# FIIDO_D2_SDA_SCL.net
KiCad netlist of a schematic drawn in EAGLE
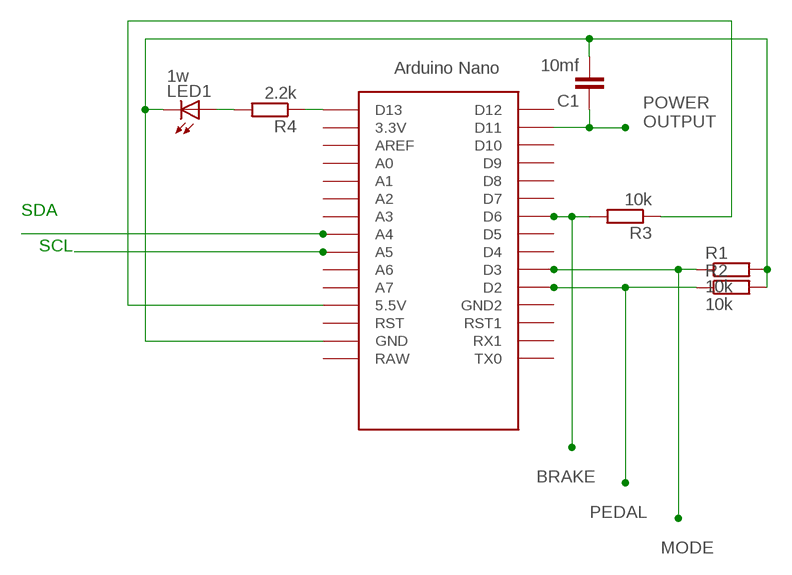
[diagram p0: schematic, sheet 1]

(export (version "E")
  (design (tool "Eeschema 10.0.6"))
  (components
    (comp (ref "C1")
      (value "10mf")
      (footprint "eagle-import:C025-024X044")
      (libsource (lib "eagle-import") (part "C-EU025-024X044"))
    )
    (comp (ref "LED1")
      (value "1w")
      (footprint "eagle-import:LED3MM")
      (libsource (lib "eagle-import") (part "LED3MM"))
    )
    (comp (ref "R1")
      (value "10k")
      (footprint "eagle-import:0207_5V")
      (libsource (lib "eagle-import") (part "R-EU_0207/5V"))
    )
    (comp (ref "R2")
      (value "10k")
      (footprint "eagle-import:0207_5V")
      (libsource (lib "eagle-import") (part "R-EU_0207/5V"))
    )
    (comp (ref "R3")
      (value "10k")
      (footprint "eagle-import:0207_5V")
      (libsource (lib "eagle-import") (part "R-EU_0207/5V"))
    )
    (comp (ref "R4")
      (value "2.2k")
      (footprint "eagle-import:0207_5V")
      (libsource (lib "eagle-import") (part "R-EU_0207/5V"))
    )
    (comp (ref "U$1")
      (value "NANO")
      (footprint "eagle-import:NANO")
      (libsource (lib "eagle-import") (part "NANO"))
    )
  )
  (nets
    (net (code "1") (name "Net-(C1-Pad1)") (class "Default")
      (node (ref "C1") (pin "1") (pinfunction "1_1") (pintype "passive"))
      (node (ref "U$1") (pin "D11") (pinfunction "D11_D11") (pintype "bidirectional"))
    )
    (net (code "2") (name "Net-(LED1-C)") (class "Default")
      (node (ref "C1") (pin "2") (pinfunction "2_2") (pintype "passive"))
      (node (ref "LED1") (pin "K") (pinfunction "C_K") (pintype "passive"))
      (node (ref "R1") (pin "2") (pinfunction "2_2") (pintype "passive"))
      (node (ref "R2") (pin "2") (pinfunction "2_2") (pintype "passive"))
      (node (ref "U$1") (pin "GND") (pinfunction "GND_GND") (pintype "bidirectional"))
    )
    (net (code "3") (name "Net-(LED1-PadA)") (class "Default")
      (node (ref "LED1") (pin "A") (pinfunction "A_A") (pintype "passive"))
      (node (ref "R4") (pin "2") (pinfunction "2_2") (pintype "passive"))
    )
    (net (code "4") (name "Net-(R1-Pad1)") (class "Default")
      (node (ref "R1") (pin "1") (pinfunction "1_1") (pintype "passive"))
      (node (ref "U$1") (pin "D3") (pinfunction "D3_D3") (pintype "bidirectional"))
    )
    (net (code "5") (name "Net-(R2-Pad1)") (class "Default")
      (node (ref "R2") (pin "1") (pinfunction "1_1") (pintype "passive"))
      (node (ref "U$1") (pin "D2") (pinfunction "D2_D2") (pintype "bidirectional"))
    )
    (net (code "6") (name "Net-(R3-Pad2)") (class "Default")
      (node (ref "R3") (pin "2") (pinfunction "2_2") (pintype "passive"))
      (node (ref "U$1") (pin "D6") (pinfunction "D6_D6") (pintype "bidirectional"))
    )
    (net (code "7") (name "Net-(R4-Pad1)") (class "Default")
      (node (ref "R4") (pin "1") (pinfunction "1_1") (pintype "passive"))
      (node (ref "U$1") (pin "D13") (pinfunction "D13_D13") (pintype "bidirectional"))
    )
    (net (code "8") (name "Net-(U$1-5.5V)") (class "Default")
      (node (ref "R3") (pin "1") (pinfunction "1_1") (pintype "passive"))
      (node (ref "U$1") (pin "5V") (pinfunction "5.5V_5V") (pintype "bidirectional"))
    )
    (net (code "9") (name "unconnected-(U$1-GND2-PadGND1)") (class "Default")
      (node (ref "U$1") (pin "GND1") (pinfunction "GND2_GND1") (pintype "bidirectional"))
    )
    (net (code "10") (name "unconnected-(U$1-Pad3.3V)") (class "Default")
      (node (ref "U$1") (pin "3.3V") (pinfunction "3.3V_3.3V") (pintype "bidirectional"))
    )
    (net (code "11") (name "unconnected-(U$1-PadA0)") (class "Default")
      (node (ref "U$1") (pin "A0") (pinfunction "A0_A0") (pintype "bidirectional"))
    )
    (net (code "12") (name "unconnected-(U$1-PadA1)") (class "Default")
      (node (ref "U$1") (pin "A1") (pinfunction "A1_A1") (pintype "bidirectional"))
    )
    (net (code "13") (name "unconnected-(U$1-PadA2)") (class "Default")
      (node (ref "U$1") (pin "A2") (pinfunction "A2_A2") (pintype "bidirectional"))
    )
    (net (code "14") (name "unconnected-(U$1-PadA3)") (class "Default")
      (node (ref "U$1") (pin "A3") (pinfunction "A3_A3") (pintype "bidirectional"))
    )
    (net (code "15") (name "unconnected-(U$1-PadA4)") (class "Default")
      (node (ref "U$1") (pin "A4") (pinfunction "A4_A4") (pintype "bidirectional"))
    )
    (net (code "16") (name "unconnected-(U$1-PadA5)") (class "Default")
      (node (ref "U$1") (pin "A5") (pinfunction "A5_A5") (pintype "bidirectional"))
    )
    (net (code "17") (name "unconnected-(U$1-PadA6)") (class "Default")
      (node (ref "U$1") (pin "A6") (pinfunction "A6_A6") (pintype "bidirectional"))
    )
    (net (code "18") (name "unconnected-(U$1-PadA7)") (class "Default")
      (node (ref "U$1") (pin "A7") (pinfunction "A7_A7") (pintype "bidirectional"))
    )
    (net (code "19") (name "unconnected-(U$1-PadAREF)") (class "Default")
      (node (ref "U$1") (pin "AREF") (pinfunction "AREF_AREF") (pintype "bidirectional"))
    )
    (net (code "20") (name "unconnected-(U$1-PadD4)") (class "Default")
      (node (ref "U$1") (pin "D4") (pinfunction "D4_D4") (pintype "bidirectional"))
    )
    (net (code "21") (name "unconnected-(U$1-PadD5)") (class "Default")
      (node (ref "U$1") (pin "D5") (pinfunction "D5_D5") (pintype "bidirectional"))
    )
    (net (code "22") (name "unconnected-(U$1-PadD7)") (class "Default")
      (node (ref "U$1") (pin "D7") (pinfunction "D7_D7") (pintype "bidirectional"))
    )
    (net (code "23") (name "unconnected-(U$1-PadD8)") (class "Default")
      (node (ref "U$1") (pin "D8") (pinfunction "D8_D8") (pintype "bidirectional"))
    )
    (net (code "24") (name "unconnected-(U$1-PadD9)") (class "Default")
      (node (ref "U$1") (pin "D9") (pinfunction "D9_D9") (pintype "bidirectional"))
    )
    (net (code "25") (name "unconnected-(U$1-PadD10)") (class "Default")
      (node (ref "U$1") (pin "D10") (pinfunction "D10_D10") (pintype "bidirectional"))
    )
    (net (code "26") (name "unconnected-(U$1-PadD12)") (class "Default")
      (node (ref "U$1") (pin "D12") (pinfunction "D12_D12") (pintype "bidirectional"))
    )
    (net (code "27") (name "unconnected-(U$1-PadICSP1)") (class "Default")
      (node (ref "U$1") (pin "ICSP1") (pinfunction "ICSP1_ICSP1") (pintype "bidirectional"))
    )
    (net (code "28") (name "unconnected-(U$1-PadICSP2)") (class "Default")
      (node (ref "U$1") (pin "ICSP2") (pinfunction "ICSP2_ICSP2") (pintype "bidirectional"))
    )
    (net (code "29") (name "unconnected-(U$1-PadICSP3)") (class "Default")
      (node (ref "U$1") (pin "ICSP3") (pinfunction "ICSP3_ICSP3") (pintype "bidirectional"))
    )
    (net (code "30") (name "unconnected-(U$1-PadICSP4)") (class "Default")
      (node (ref "U$1") (pin "ICSP4") (pinfunction "ICSP4_ICSP4") (pintype "bidirectional"))
    )
    (net (code "31") (name "unconnected-(U$1-PadICSP5)") (class "Default")
      (node (ref "U$1") (pin "ICSP5") (pinfunction "ICSP5_ICSP5") (pintype "bidirectional"))
    )
    (net (code "32") (name "unconnected-(U$1-PadICSP6)") (class "Default")
      (node (ref "U$1") (pin "ICSP6") (pinfunction "ICSP6_ICSP6") (pintype "bidirectional"))
    )
    (net (code "33") (name "unconnected-(U$1-PadRAW)") (class "Default")
      (node (ref "U$1") (pin "RAW") (pinfunction "RAW_RAW") (pintype "bidirectional"))
    )
    (net (code "34") (name "unconnected-(U$1-PadRST)") (class "Default")
      (node (ref "U$1") (pin "RST") (pinfunction "RST_RST") (pintype "bidirectional"))
    )
    (net (code "35") (name "unconnected-(U$1-PadRST1)") (class "Default")
      (node (ref "U$1") (pin "RST1") (pinfunction "RST1_RST1") (pintype "bidirectional"))
    )
    (net (code "36") (name "unconnected-(U$1-PadRX1)") (class "Default")
      (node (ref "U$1") (pin "RX1") (pinfunction "RX1_RX1") (pintype "bidirectional"))
    )
    (net (code "37") (name "unconnected-(U$1-PadTX0)") (class "Default")
      (node (ref "U$1") (pin "TX0") (pinfunction "TX0_TX0") (pintype "bidirectional"))
    )
  )
)
